# sonic-telemeter.net
KiCad netlist of a schematic drawn in EAGLE
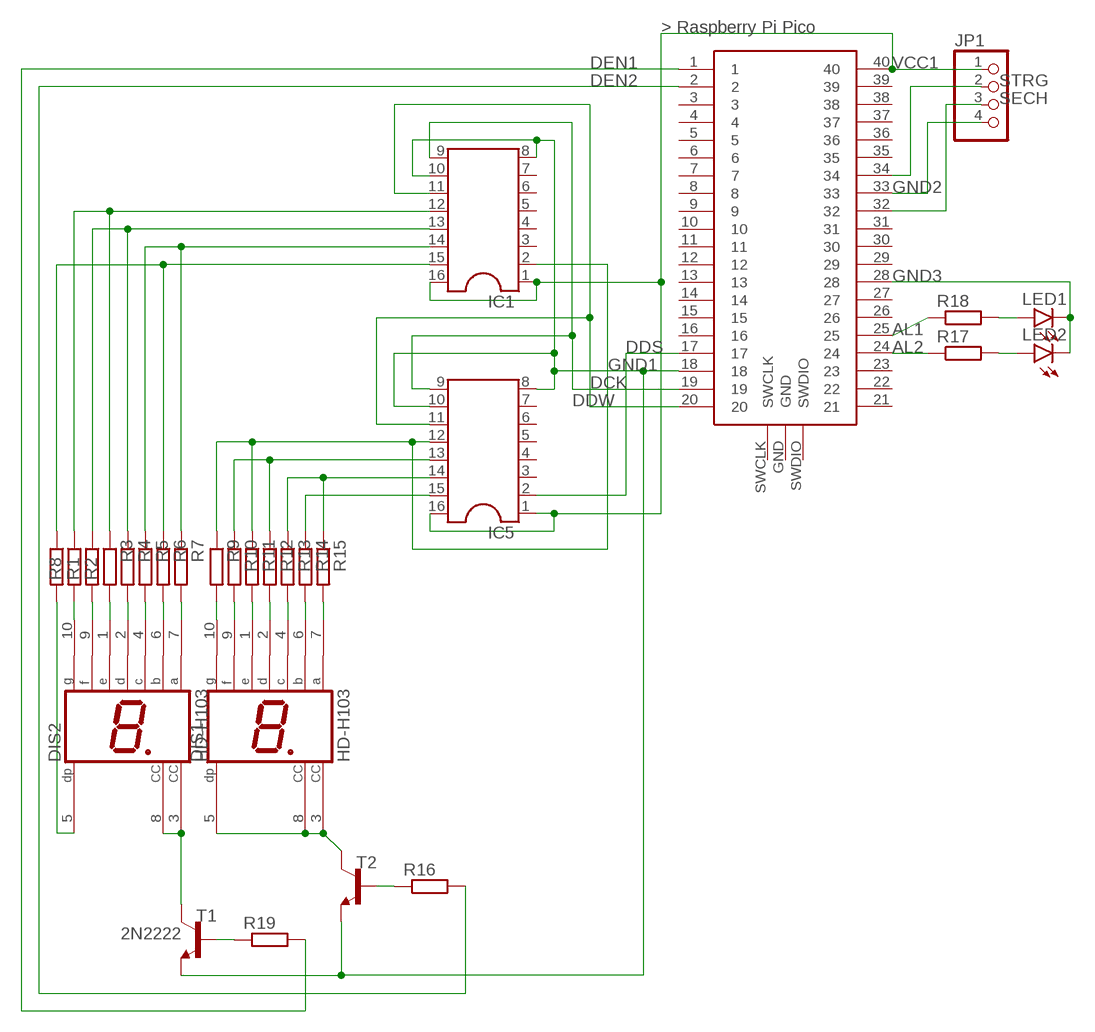
[diagram p0: schematic, sheet 1]

(export (version "E")
  (design (tool "Eeschema 10.0.6"))
  (components
    (comp (ref "DIS1")
      (value "HD-H103")
      (footprint "eagle-import:HDSP-M")
      (libsource (lib "eagle-import") (part "HD-H103"))
    )
    (comp (ref "DIS2")
      (value "HD-H103")
      (footprint "eagle-import:HDSP-M")
      (libsource (lib "eagle-import") (part "HD-H103"))
    )
    (comp (ref "IC1")
      (value "DIL16")
      (footprint "eagle-import:DIL16")
      (libsource (lib "eagle-import") (part "DIL16"))
    )
    (comp (ref "IC5")
      (value "DIL16")
      (footprint "eagle-import:DIL16")
      (libsource (lib "eagle-import") (part "DIL16"))
    )
    (comp (ref "JP1")
      (value "PINHD-1X4")
      (footprint "eagle-import:1X04")
      (libsource (lib "eagle-import") (part "PINHD-1X4"))
    )
    (comp (ref "LED1")
      (value "LED5MM")
      (footprint "eagle-import:LED5MM")
      (libsource (lib "eagle-import") (part "LED5MM"))
    )
    (comp (ref "LED2")
      (value "LED5MM")
      (footprint "eagle-import:LED5MM")
      (libsource (lib "eagle-import") (part "LED5MM"))
    )
    (comp (ref "R1")
      (value "R-EU_0204/5")
      (footprint "eagle-import:0204_5")
      (libsource (lib "eagle-import") (part "R-EU_0204/5"))
    )
    (comp (ref "R2")
      (value "R-EU_0204/5")
      (footprint "eagle-import:0204_5")
      (libsource (lib "eagle-import") (part "R-EU_0204/5"))
    )
    (comp (ref "R3")
      (value "R-EU_0204/5")
      (footprint "eagle-import:0204_5")
      (libsource (lib "eagle-import") (part "R-EU_0204/5"))
    )
    (comp (ref "R4")
      (value "R-EU_0204/5")
      (footprint "eagle-import:0204_5")
      (libsource (lib "eagle-import") (part "R-EU_0204/5"))
    )
    (comp (ref "R5")
      (value "R-EU_0204/5")
      (footprint "eagle-import:0204_5")
      (libsource (lib "eagle-import") (part "R-EU_0204/5"))
    )
    (comp (ref "R6")
      (value "R-EU_0204/5")
      (footprint "eagle-import:0204_5")
      (libsource (lib "eagle-import") (part "R-EU_0204/5"))
    )
    (comp (ref "R7")
      (value "R-EU_0204/5")
      (footprint "eagle-import:0204_5")
      (libsource (lib "eagle-import") (part "R-EU_0204/5"))
    )
    (comp (ref "R8")
      (value "R-EU_0204/5")
      (footprint "eagle-import:0204_5")
      (libsource (lib "eagle-import") (part "R-EU_0204/5"))
    )
    (comp (ref "R9")
      (value "R-EU_0204/5")
      (footprint "eagle-import:0204_5")
      (libsource (lib "eagle-import") (part "R-EU_0204/5"))
    )
    (comp (ref "R10")
      (value "R-EU_0204/5")
      (footprint "eagle-import:0204_5")
      (libsource (lib "eagle-import") (part "R-EU_0204/5"))
    )
    (comp (ref "R11")
      (value "R-EU_0204/5")
      (footprint "eagle-import:0204_5")
      (libsource (lib "eagle-import") (part "R-EU_0204/5"))
    )
    (comp (ref "R12")
      (value "R-EU_0204/5")
      (footprint "eagle-import:0204_5")
      (libsource (lib "eagle-import") (part "R-EU_0204/5"))
    )
    (comp (ref "R13")
      (value "R-EU_0204/5")
      (footprint "eagle-import:0204_5")
      (libsource (lib "eagle-import") (part "R-EU_0204/5"))
    )
    (comp (ref "R14")
      (value "R-EU_0204/5")
      (footprint "eagle-import:0204_5")
      (libsource (lib "eagle-import") (part "R-EU_0204/5"))
    )
    (comp (ref "R15")
      (value "R-EU_0204/5")
      (footprint "eagle-import:0204_5")
      (libsource (lib "eagle-import") (part "R-EU_0204/5"))
    )
    (comp (ref "R16")
      (value "R-EU_0204/5")
      (footprint "eagle-import:0204_5")
      (libsource (lib "eagle-import") (part "R-EU_0204/5"))
    )
    (comp (ref "R17")
      (value "R-EU_0204/5")
      (footprint "eagle-import:0204_5")
      (libsource (lib "eagle-import") (part "R-EU_0204/5"))
    )
    (comp (ref "R18")
      (value "R-EU_0204/5")
      (footprint "eagle-import:0204_5")
      (libsource (lib "eagle-import") (part "R-EU_0204/5"))
    )
    (comp (ref "R19")
      (value "R-EU_0204/5")
      (footprint "eagle-import:0204_5")
      (libsource (lib "eagle-import") (part "R-EU_0204/5"))
    )
    (comp (ref "T1")
      (value "2N2222")
      (footprint "eagle-import:TO18")
      (libsource (lib "eagle-import") (part "2N2222"))
    )
    (comp (ref "T2")
      (value "2N2222")
      (footprint "eagle-import:TO18")
      (libsource (lib "eagle-import") (part "2N2222"))
    )
    (comp (ref "U$1")
      (value "RASPBERRY-PI-PICO_TH")
      (footprint "eagle-import:FT_RASPBERRY-PI-PICO_TH")
      (libsource (lib "eagle-import") (part "RASPBERRY-PI-PICO_TH"))
    )
  )
  (nets
    (net (code "1") (name "/AL1") (class "Default")
      (node (ref "R18") (pin "1") (pinfunction "1_1") (pintype "passive"))
      (node (ref "U$1") (pin "25") (pinfunction "25_25") (pintype "bidirectional"))
    )
    (net (code "2") (name "/AL2") (class "Default")
      (node (ref "R17") (pin "1") (pinfunction "1_1") (pintype "passive"))
      (node (ref "U$1") (pin "24") (pinfunction "24_24") (pintype "bidirectional"))
    )
    (net (code "3") (name "/DCK") (class "Default")
      (node (ref "IC1") (pin "9") (pinfunction "9_9") (pintype "passive"))
      (node (ref "IC5") (pin "9") (pinfunction "9_9") (pintype "passive"))
      (node (ref "U$1") (pin "19") (pinfunction "19_19") (pintype "bidirectional"))
    )
    (net (code "4") (name "/DDS") (class "Default")
      (node (ref "IC5") (pin "2") (pinfunction "2_2") (pintype "passive"))
      (node (ref "U$1") (pin "17") (pinfunction "17_17") (pintype "bidirectional"))
    )
    (net (code "5") (name "/DDW") (class "Default")
      (node (ref "IC1") (pin "11") (pinfunction "11_11") (pintype "passive"))
      (node (ref "IC5") (pin "11") (pinfunction "11_11") (pintype "passive"))
      (node (ref "U$1") (pin "20") (pinfunction "20_20") (pintype "bidirectional"))
    )
    (net (code "6") (name "/DEN1") (class "Default")
      (node (ref "R19") (pin "2") (pinfunction "2_2") (pintype "passive"))
      (node (ref "U$1") (pin "1") (pinfunction "1_1") (pintype "bidirectional"))
    )
    (net (code "7") (name "/DEN2") (class "Default")
      (node (ref "R16") (pin "2") (pinfunction "2_2") (pintype "passive"))
      (node (ref "U$1") (pin "2") (pinfunction "2_2") (pintype "bidirectional"))
    )
    (net (code "8") (name "/GND1") (class "Default")
      (node (ref "IC1") (pin "10") (pinfunction "10_10") (pintype "passive"))
      (node (ref "IC1") (pin "8") (pinfunction "8_8") (pintype "passive"))
      (node (ref "IC5") (pin "10") (pinfunction "10_10") (pintype "passive"))
      (node (ref "IC5") (pin "8") (pinfunction "8_8") (pintype "passive"))
      (node (ref "T1") (pin "1") (pinfunction "E_1") (pintype "passive"))
      (node (ref "T2") (pin "1") (pinfunction "E_1") (pintype "passive"))
      (node (ref "U$1") (pin "18") (pinfunction "18_18") (pintype "bidirectional"))
    )
    (net (code "9") (name "/GND2") (class "Default")
      (node (ref "JP1") (pin "4") (pinfunction "4_4") (pintype "passive"))
      (node (ref "U$1") (pin "33") (pinfunction "33_33") (pintype "bidirectional"))
    )
    (net (code "10") (name "/GND3") (class "Default")
      (node (ref "LED1") (pin "K") (pinfunction "C_K") (pintype "passive"))
      (node (ref "LED2") (pin "K") (pinfunction "C_K") (pintype "passive"))
      (node (ref "U$1") (pin "28") (pinfunction "28_28") (pintype "bidirectional"))
    )
    (net (code "11") (name "/SECH") (class "Default")
      (node (ref "JP1") (pin "3") (pinfunction "3_3") (pintype "passive"))
      (node (ref "U$1") (pin "32") (pinfunction "32_32") (pintype "bidirectional"))
    )
    (net (code "12") (name "/STRG") (class "Default")
      (node (ref "JP1") (pin "2") (pinfunction "2_2") (pintype "passive"))
      (node (ref "U$1") (pin "34") (pinfunction "34_34") (pintype "bidirectional"))
    )
    (net (code "13") (name "/VCC1") (class "Default")
      (node (ref "IC1") (pin "1") (pinfunction "1_1") (pintype "passive"))
      (node (ref "IC1") (pin "16") (pinfunction "16_16") (pintype "passive"))
      (node (ref "IC5") (pin "1") (pinfunction "1_1") (pintype "passive"))
      (node (ref "IC5") (pin "16") (pinfunction "16_16") (pintype "passive"))
      (node (ref "JP1") (pin "1") (pinfunction "1_1") (pintype "passive"))
      (node (ref "U$1") (pin "40") (pinfunction "40_40") (pintype "bidirectional"))
    )
    (net (code "14") (name "Net-(DIS1-A)") (class "Default")
      (node (ref "DIS1") (pin "7") (pinfunction "A_7") (pintype "passive"))
      (node (ref "R15") (pin "2") (pinfunction "2_2") (pintype "passive"))
    )
    (net (code "15") (name "Net-(DIS1-B)") (class "Default")
      (node (ref "DIS1") (pin "6") (pinfunction "B_6") (pintype "passive"))
      (node (ref "R14") (pin "2") (pinfunction "2_2") (pintype "passive"))
    )
    (net (code "16") (name "Net-(DIS1-C)") (class "Default")
      (node (ref "DIS1") (pin "4") (pinfunction "C_4") (pintype "passive"))
      (node (ref "R13") (pin "2") (pinfunction "2_2") (pintype "passive"))
    )
    (net (code "17") (name "Net-(DIS1-D)") (class "Default")
      (node (ref "DIS1") (pin "2") (pinfunction "D_2") (pintype "passive"))
      (node (ref "R12") (pin "2") (pinfunction "2_2") (pintype "passive"))
    )
    (net (code "18") (name "Net-(DIS1-DP)") (class "Default")
      (node (ref "DIS1") (pin "3") (pinfunction "CC_3") (pintype "passive"))
      (node (ref "DIS1") (pin "5") (pinfunction "DP_5") (pintype "passive"))
      (node (ref "DIS1") (pin "8") (pinfunction "CC_8") (pintype "passive"))
      (node (ref "T2") (pin "3") (pinfunction "C_3") (pintype "passive"))
    )
    (net (code "19") (name "Net-(DIS1-E)") (class "Default")
      (node (ref "DIS1") (pin "1") (pinfunction "E_1") (pintype "passive"))
      (node (ref "R11") (pin "2") (pinfunction "2_2") (pintype "passive"))
    )
    (net (code "20") (name "Net-(DIS1-F)") (class "Default")
      (node (ref "DIS1") (pin "9") (pinfunction "F_9") (pintype "passive"))
      (node (ref "R10") (pin "2") (pinfunction "2_2") (pintype "passive"))
    )
    (net (code "21") (name "Net-(DIS1-G)") (class "Default")
      (node (ref "DIS1") (pin "10") (pinfunction "G_10") (pintype "passive"))
      (node (ref "R9") (pin "2") (pinfunction "2_2") (pintype "passive"))
    )
    (net (code "22") (name "Net-(DIS2-A)") (class "Default")
      (node (ref "DIS2") (pin "7") (pinfunction "A_7") (pintype "passive"))
      (node (ref "R7") (pin "2") (pinfunction "2_2") (pintype "passive"))
    )
    (net (code "23") (name "Net-(DIS2-B)") (class "Default")
      (node (ref "DIS2") (pin "6") (pinfunction "B_6") (pintype "passive"))
      (node (ref "R6") (pin "2") (pinfunction "2_2") (pintype "passive"))
    )
    (net (code "24") (name "Net-(DIS2-C)") (class "Default")
      (node (ref "DIS2") (pin "4") (pinfunction "C_4") (pintype "passive"))
      (node (ref "R5") (pin "2") (pinfunction "2_2") (pintype "passive"))
    )
    (net (code "25") (name "Net-(DIS2-D)") (class "Default")
      (node (ref "DIS2") (pin "2") (pinfunction "D_2") (pintype "passive"))
      (node (ref "R4") (pin "2") (pinfunction "2_2") (pintype "passive"))
    )
    (net (code "26") (name "Net-(DIS2-DP)") (class "Default")
      (node (ref "DIS2") (pin "5") (pinfunction "DP_5") (pintype "passive"))
      (node (ref "R8") (pin "2") (pinfunction "2_2") (pintype "passive"))
    )
    (net (code "27") (name "Net-(DIS2-E)") (class "Default")
      (node (ref "DIS2") (pin "1") (pinfunction "E_1") (pintype "passive"))
      (node (ref "R3") (pin "2") (pinfunction "2_2") (pintype "passive"))
    )
    (net (code "28") (name "Net-(DIS2-F)") (class "Default")
      (node (ref "DIS2") (pin "9") (pinfunction "F_9") (pintype "passive"))
      (node (ref "R2") (pin "2") (pinfunction "2_2") (pintype "passive"))
    )
    (net (code "29") (name "Net-(DIS2-G)") (class "Default")
      (node (ref "DIS2") (pin "10") (pinfunction "G_10") (pintype "passive"))
      (node (ref "R1") (pin "2") (pinfunction "2_2") (pintype "passive"))
    )
    (net (code "30") (name "Net-(IC1-Pad2)") (class "Default")
      (node (ref "IC1") (pin "2") (pinfunction "2_2") (pintype "passive"))
      (node (ref "IC5") (pin "12") (pinfunction "12_12") (pintype "passive"))
      (node (ref "R11") (pin "1") (pinfunction "1_1") (pintype "passive"))
      (node (ref "R9") (pin "1") (pinfunction "1_1") (pintype "passive"))
    )
    (net (code "31") (name "Net-(IC1-Pad12)") (class "Default")
      (node (ref "IC1") (pin "12") (pinfunction "12_12") (pintype "passive"))
      (node (ref "R1") (pin "1") (pinfunction "1_1") (pintype "passive"))
      (node (ref "R3") (pin "1") (pinfunction "1_1") (pintype "passive"))
    )
    (net (code "32") (name "Net-(IC1-Pad13)") (class "Default")
      (node (ref "IC1") (pin "13") (pinfunction "13_13") (pintype "passive"))
      (node (ref "R2") (pin "1") (pinfunction "1_1") (pintype "passive"))
      (node (ref "R4") (pin "1") (pinfunction "1_1") (pintype "passive"))
    )
    (net (code "33") (name "Net-(IC1-Pad14)") (class "Default")
      (node (ref "IC1") (pin "14") (pinfunction "14_14") (pintype "passive"))
      (node (ref "R5") (pin "1") (pinfunction "1_1") (pintype "passive"))
      (node (ref "R7") (pin "1") (pinfunction "1_1") (pintype "passive"))
    )
    (net (code "34") (name "Net-(IC1-Pad15)") (class "Default")
      (node (ref "IC1") (pin "15") (pinfunction "15_15") (pintype "passive"))
      (node (ref "R6") (pin "1") (pinfunction "1_1") (pintype "passive"))
      (node (ref "R8") (pin "1") (pinfunction "1_1") (pintype "passive"))
    )
    (net (code "35") (name "Net-(IC5-Pad13)") (class "Default")
      (node (ref "IC5") (pin "13") (pinfunction "13_13") (pintype "passive"))
      (node (ref "R10") (pin "1") (pinfunction "1_1") (pintype "passive"))
      (node (ref "R12") (pin "1") (pinfunction "1_1") (pintype "passive"))
    )
    (net (code "36") (name "Net-(IC5-Pad14)") (class "Default")
      (node (ref "IC5") (pin "14") (pinfunction "14_14") (pintype "passive"))
      (node (ref "R13") (pin "1") (pinfunction "1_1") (pintype "passive"))
      (node (ref "R15") (pin "1") (pinfunction "1_1") (pintype "passive"))
    )
    (net (code "37") (name "Net-(IC5-Pad15)") (class "Default")
      (node (ref "IC5") (pin "15") (pinfunction "15_15") (pintype "passive"))
      (node (ref "R14") (pin "1") (pinfunction "1_1") (pintype "passive"))
    )
    (net (code "38") (name "Net-(LED1-PadA)") (class "Default")
      (node (ref "LED1") (pin "A") (pinfunction "A_A") (pintype "passive"))
      (node (ref "R18") (pin "2") (pinfunction "2_2") (pintype "passive"))
    )
    (net (code "39") (name "Net-(LED2-PadA)") (class "Default")
      (node (ref "LED2") (pin "A") (pinfunction "A_A") (pintype "passive"))
      (node (ref "R17") (pin "2") (pinfunction "2_2") (pintype "passive"))
    )
    (net (code "40") (name "Net-(T1-B)") (class "Default")
      (node (ref "R19") (pin "1") (pinfunction "1_1") (pintype "passive"))
      (node (ref "T1") (pin "2") (pinfunction "B_2") (pintype "passive"))
    )
    (net (code "41") (name "Net-(T1-C)") (class "Default")
      (node (ref "DIS2") (pin "3") (pinfunction "CC_3") (pintype "passive"))
      (node (ref "DIS2") (pin "8") (pinfunction "CC_8") (pintype "passive"))
      (node (ref "T1") (pin "3") (pinfunction "C_3") (pintype "passive"))
    )
    (net (code "42") (name "Net-(T2-B)") (class "Default")
      (node (ref "R16") (pin "1") (pinfunction "1_1") (pintype "passive"))
      (node (ref "T2") (pin "2") (pinfunction "B_2") (pintype "passive"))
    )
    (net (code "43") (name "unconnected-(IC1-Pad3)") (class "Default")
      (node (ref "IC1") (pin "3") (pinfunction "3_3") (pintype "passive"))
    )
    (net (code "44") (name "unconnected-(IC1-Pad4)") (class "Default")
      (node (ref "IC1") (pin "4") (pinfunction "4_4") (pintype "passive"))
    )
    (net (code "45") (name "unconnected-(IC1-Pad5)") (class "Default")
      (node (ref "IC1") (pin "5") (pinfunction "5_5") (pintype "passive"))
    )
    (net (code "46") (name "unconnected-(IC1-Pad6)") (class "Default")
      (node (ref "IC1") (pin "6") (pinfunction "6_6") (pintype "passive"))
    )
    (net (code "47") (name "unconnected-(IC1-Pad7)") (class "Default")
      (node (ref "IC1") (pin "7") (pinfunction "7_7") (pintype "passive"))
    )
    (net (code "48") (name "unconnected-(IC5-Pad3)") (class "Default")
      (node (ref "IC5") (pin "3") (pinfunction "3_3") (pintype "passive"))
    )
    (net (code "49") (name "unconnected-(IC5-Pad4)") (class "Default")
      (node (ref "IC5") (pin "4") (pinfunction "4_4") (pintype "passive"))
    )
    (net (code "50") (name "unconnected-(IC5-Pad5)") (class "Default")
      (node (ref "IC5") (pin "5") (pinfunction "5_5") (pintype "passive"))
    )
    (net (code "51") (name "unconnected-(IC5-Pad6)") (class "Default")
      (node (ref "IC5") (pin "6") (pinfunction "6_6") (pintype "passive"))
    )
    (net (code "52") (name "unconnected-(IC5-Pad7)") (class "Default")
      (node (ref "IC5") (pin "7") (pinfunction "7_7") (pintype "passive"))
    )
    (net (code "53") (name "unconnected-(U$1-Pad3)") (class "Default")
      (node (ref "U$1") (pin "3") (pinfunction "3_3") (pintype "bidirectional"))
    )
    (net (code "54") (name "unconnected-(U$1-Pad4)") (class "Default")
      (node (ref "U$1") (pin "4") (pinfunction "4_4") (pintype "bidirectional"))
    )
    (net (code "55") (name "unconnected-(U$1-Pad5)") (class "Default")
      (node (ref "U$1") (pin "5") (pinfunction "5_5") (pintype "bidirectional"))
    )
    (net (code "56") (name "unconnected-(U$1-Pad6)") (class "Default")
      (node (ref "U$1") (pin "6") (pinfunction "6_6") (pintype "bidirectional"))
    )
    (net (code "57") (name "unconnected-(U$1-Pad7)") (class "Default")
      (node (ref "U$1") (pin "7") (pinfunction "7_7") (pintype "bidirectional"))
    )
    (net (code "58") (name "unconnected-(U$1-Pad8)") (class "Default")
      (node (ref "U$1") (pin "8") (pinfunction "8_8") (pintype "bidirectional"))
    )
    (net (code "59") (name "unconnected-(U$1-Pad9)") (class "Default")
      (node (ref "U$1") (pin "9") (pinfunction "9_9") (pintype "bidirectional"))
    )
    (net (code "60") (name "unconnected-(U$1-Pad10)") (class "Default")
      (node (ref "U$1") (pin "10") (pinfunction "10_10") (pintype "bidirectional"))
    )
    (net (code "61") (name "unconnected-(U$1-Pad11)") (class "Default")
      (node (ref "U$1") (pin "11") (pinfunction "11_11") (pintype "bidirectional"))
    )
    (net (code "62") (name "unconnected-(U$1-Pad12)") (class "Default")
      (node (ref "U$1") (pin "12") (pinfunction "12_12") (pintype "bidirectional"))
    )
    (net (code "63") (name "unconnected-(U$1-Pad13)") (class "Default")
      (node (ref "U$1") (pin "13") (pinfunction "13_13") (pintype "bidirectional"))
    )
    (net (code "64") (name "unconnected-(U$1-Pad14)") (class "Default")
      (node (ref "U$1") (pin "14") (pinfunction "14_14") (pintype "bidirectional"))
    )
    (net (code "65") (name "unconnected-(U$1-Pad15)") (class "Default")
      (node (ref "U$1") (pin "15") (pinfunction "15_15") (pintype "bidirectional"))
    )
    (net (code "66") (name "unconnected-(U$1-Pad16)") (class "Default")
      (node (ref "U$1") (pin "16") (pinfunction "16_16") (pintype "bidirectional"))
    )
    (net (code "67") (name "unconnected-(U$1-Pad21)") (class "Default")
      (node (ref "U$1") (pin "21") (pinfunction "21_21") (pintype "bidirectional"))
    )
    (net (code "68") (name "unconnected-(U$1-Pad22)") (class "Default")
      (node (ref "U$1") (pin "22") (pinfunction "22_22") (pintype "bidirectional"))
    )
    (net (code "69") (name "unconnected-(U$1-Pad23)") (class "Default")
      (node (ref "U$1") (pin "23") (pinfunction "23_23") (pintype "bidirectional"))
    )
    (net (code "70") (name "unconnected-(U$1-Pad26)") (class "Default")
      (node (ref "U$1") (pin "26") (pinfunction "26_26") (pintype "bidirectional"))
    )
    (net (code "71") (name "unconnected-(U$1-Pad27)") (class "Default")
      (node (ref "U$1") (pin "27") (pinfunction "27_27") (pintype "bidirectional"))
    )
    (net (code "72") (name "unconnected-(U$1-Pad29)") (class "Default")
      (node (ref "U$1") (pin "29") (pinfunction "29_29") (pintype "bidirectional"))
    )
    (net (code "73") (name "unconnected-(U$1-Pad30)") (class "Default")
      (node (ref "U$1") (pin "30") (pinfunction "30_30") (pintype "bidirectional"))
    )
    (net (code "74") (name "unconnected-(U$1-Pad31)") (class "Default")
      (node (ref "U$1") (pin "31") (pinfunction "31_31") (pintype "bidirectional"))
    )
    (net (code "75") (name "unconnected-(U$1-Pad35)") (class "Default")
      (node (ref "U$1") (pin "35") (pinfunction "35_35") (pintype "bidirectional"))
    )
    (net (code "76") (name "unconnected-(U$1-Pad36)") (class "Default")
      (node (ref "U$1") (pin "36") (pinfunction "36_36") (pintype "bidirectional"))
    )
    (net (code "77") (name "unconnected-(U$1-Pad37)") (class "Default")
      (node (ref "U$1") (pin "37") (pinfunction "37_37") (pintype "bidirectional"))
    )
    (net (code "78") (name "unconnected-(U$1-Pad38)") (class "Default")
      (node (ref "U$1") (pin "38") (pinfunction "38_38") (pintype "bidirectional"))
    )
    (net (code "79") (name "unconnected-(U$1-Pad39)") (class "Default")
      (node (ref "U$1") (pin "39") (pinfunction "39_39") (pintype "bidirectional"))
    )
    (net (code "80") (name "unconnected-(U$1-PadGND)") (class "Default")
      (node (ref "U$1") (pin "GND") (pinfunction "GND_GND") (pintype "bidirectional"))
    )
    (net (code "81") (name "unconnected-(U$1-PadSWCLK)") (class "Default")
      (node (ref "U$1") (pin "SWCLK") (pinfunction "SWCLK_SWCLK") (pintype "bidirectional"))
    )
    (net (code "82") (name "unconnected-(U$1-PadSWDIO)") (class "Default")
      (node (ref "U$1") (pin "SWDIO") (pinfunction "SWDIO_SWDIO") (pintype "bidirectional"))
    )
  )
)
